# UD3_1_Analog_IO.net
KiCad netlist of a schematic drawn in Altium Designer
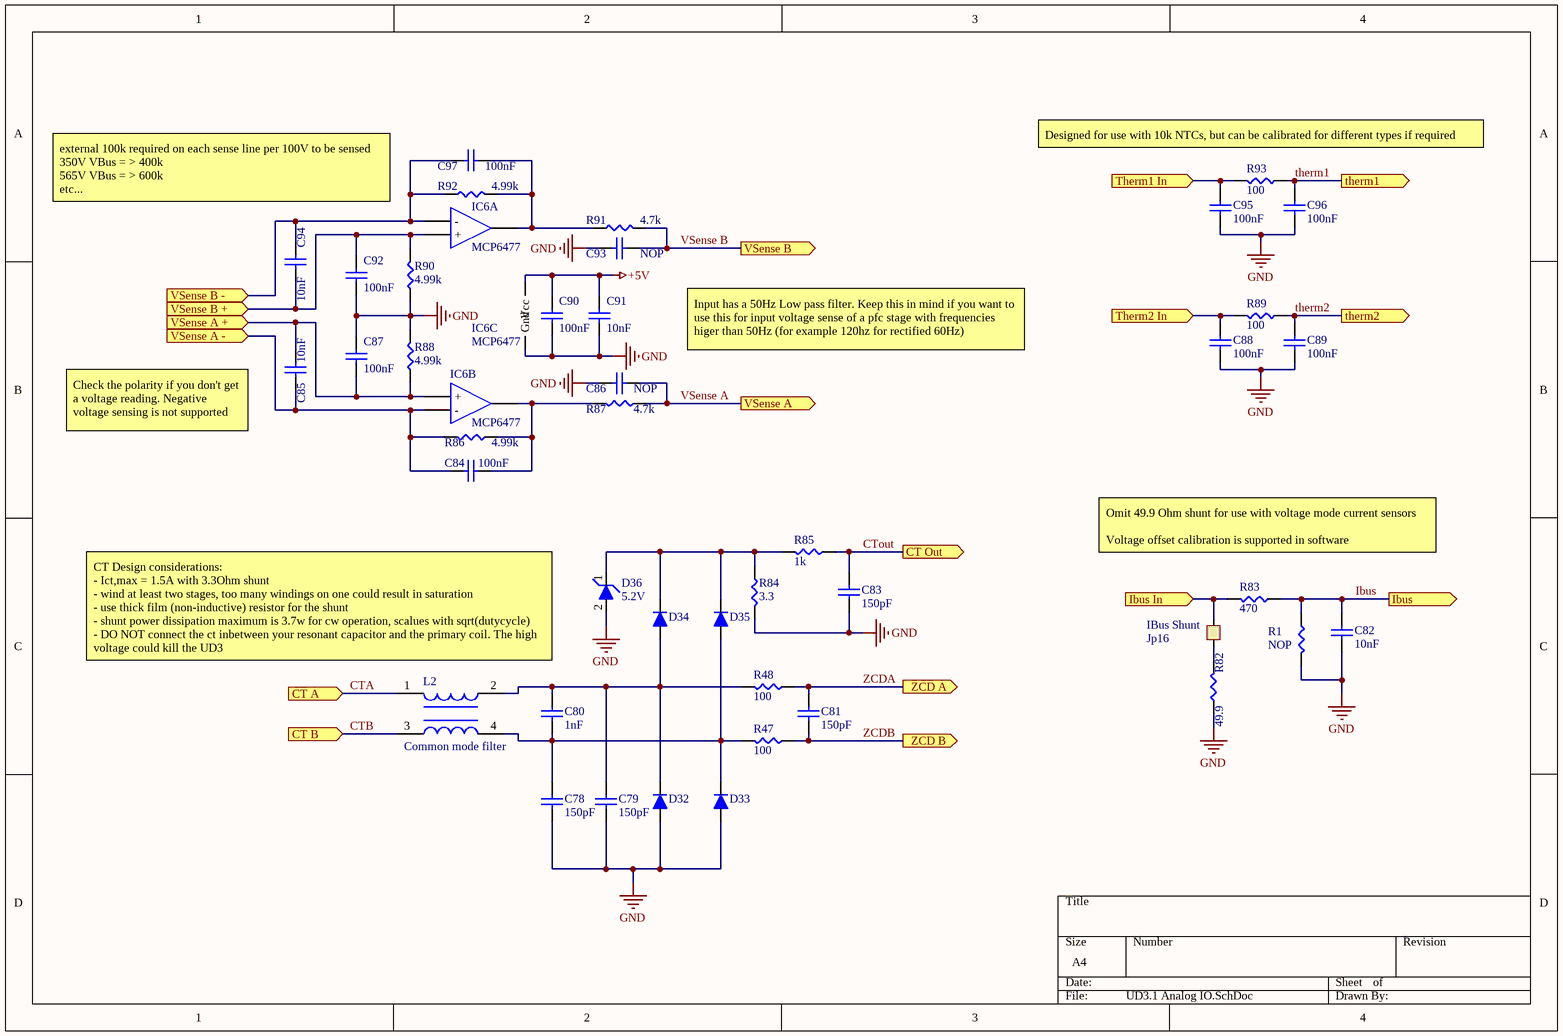
[diagram p0: UD3.1 Analog IO.SchDoc]

(export (version "E")
  (design (tool "Eeschema 10.0.6"))
  (components
    (comp (ref "C78") (value "150pF") (footprint "0603") (libsource (lib "stdLib") (part "Cap")))
    (comp (ref "C79") (value "150pF") (footprint "0603") (libsource (lib "stdLib") (part "Cap")))
    (comp (ref "C80") (value "1nF") (footprint "0603") (libsource (lib "stdLib") (part "Cap")))
    (comp (ref "C81") (value "150pF") (footprint "0603") (libsource (lib "stdLib") (part "Cap")))
    (comp (ref "C82") (value "10nF") (footprint "0603") (libsource (lib "stdLib") (part "Cap")))
    (comp (ref "C83") (value "150pF") (footprint "0603") (libsource (lib "stdLib") (part "Cap")))
    (comp (ref "C84") (value "100nF") (footprint "0603") (libsource (lib "stdLib") (part "Cap")))
    (comp (ref "C85") (value "10nF") (footprint "0603") (libsource (lib "stdLib") (part "Cap")))
    (comp (ref "C86") (value "NOP") (footprint "0603") (libsource (lib "stdLib") (part "Cap")))
    (comp (ref "C87") (value "100nF") (footprint "0603") (libsource (lib "stdLib") (part "Cap")))
    (comp (ref "C88") (value "100nF") (footprint "0603") (libsource (lib "stdLib") (part "Cap")))
    (comp (ref "C89") (value "100nF") (footprint "0603") (libsource (lib "stdLib") (part "Cap")))
    (comp (ref "C90") (value "100nF") (footprint "0603") (libsource (lib "stdLib") (part "Cap")))
    (comp (ref "C91") (value "10nF") (footprint "0603") (libsource (lib "stdLib") (part "Cap")))
    (comp (ref "C92") (value "100nF") (footprint "0603") (libsource (lib "stdLib") (part "Cap")))
    (comp (ref "C93") (value "NOP") (footprint "0603") (libsource (lib "stdLib") (part "Cap")))
    (comp (ref "C94") (value "10nF") (footprint "0603") (libsource (lib "stdLib") (part "Cap")))
    (comp (ref "C95") (value "100nF") (footprint "0603") (libsource (lib "stdLib") (part "Cap")))
    (comp (ref "C96") (value "100nF") (footprint "0603") (libsource (lib "stdLib") (part "Cap")))
    (comp (ref "C97") (value "100nF") (footprint "0603") (libsource (lib "stdLib") (part "Cap")))
    (comp (ref "D32")
      (value "Schottky 30V 1A")
      (footprint "DO-214")
      (description "Cmon its a diode what more do I need to say?")
      (libsource (lib "stdLib") (part "Diode"))
    )
    (comp (ref "D33")
      (value "Schottky 30V 1A")
      (footprint "DO-214")
      (description "Cmon its a diode what more do I need to say?")
      (libsource (lib "stdLib") (part "Diode"))
    )
    (comp (ref "D34")
      (value "Schottky 30V 1A")
      (footprint "DO-214")
      (description "Cmon its a diode what more do I need to say?")
      (libsource (lib "stdLib") (part "Diode"))
    )
    (comp (ref "D35")
      (value "Schottky 30V 1A")
      (footprint "DO-214")
      (description "Cmon its a diode what more do I need to say?")
      (libsource (lib "stdLib") (part "Diode"))
    )
    (comp (ref "D36") (value "5.2V") (footprint "DO-214") (libsource (lib "stdLib") (part "TVS Diode")))
    (comp (ref "IC6") (value "MCP6477") (footprint "soic8") (libsource (lib "stdLib") (part "OpAmp dual")))
    (comp (ref "Jp16")
      (value "IBus Shunt")
      (footprint "PCB Jumper NO")
      (libsource (lib "stdLib") (part "Jumper"))
    )
    (comp (ref "L2")
      (value "Common mode filter")
      (footprint "SON127P600 4 POS (8.50mm x 5.60mm)")
      (libsource (lib "stdLib") (part "Common mode filter"))
    )
    (comp (ref "R1") (value "NOP") (footprint "0603") (libsource (lib "stdLib") (part "Resistor")))
    (comp (ref "R47") (value "100") (footprint "0603") (libsource (lib "stdLib") (part "Resistor")))
    (comp (ref "R48") (value "100") (footprint "0603") (libsource (lib "stdLib") (part "Resistor")))
    (comp (ref "R82") (value "49.9") (footprint "1210") (libsource (lib "stdLib") (part "Resistor")))
    (comp (ref "R83") (value "470") (footprint "0603") (libsource (lib "stdLib") (part "Resistor")))
    (comp (ref "R84") (value "3.3") (footprint "0411 THT 2W") (libsource (lib "stdLib") (part "Resistor")))
    (comp (ref "R85") (value "1k") (footprint "0603") (libsource (lib "stdLib") (part "Resistor")))
    (comp (ref "R86") (value "4.99k") (footprint "0603") (libsource (lib "stdLib") (part "Resistor")))
    (comp (ref "R87") (value "4.7k") (footprint "0603") (libsource (lib "stdLib") (part "Resistor")))
    (comp (ref "R88") (value "4.99k") (footprint "0603") (libsource (lib "stdLib") (part "Resistor")))
    (comp (ref "R89") (value "100") (footprint "0603") (libsource (lib "stdLib") (part "Resistor")))
    (comp (ref "R90") (value "4.99k") (footprint "0603") (libsource (lib "stdLib") (part "Resistor")))
    (comp (ref "R91") (value "4.7k") (footprint "0603") (libsource (lib "stdLib") (part "Resistor")))
    (comp (ref "R92") (value "4.99k") (footprint "0603") (libsource (lib "stdLib") (part "Resistor")))
    (comp (ref "R93") (value "100") (footprint "0603") (libsource (lib "stdLib") (part "Resistor")))
  )
  (nets
    (net (code "1") (name "+5V") (class "Default")
      (node (ref "C90") (pin "2") (pinfunction "2_2") (pintype "passive"))
      (node (ref "C91") (pin "2") (pinfunction "2_2") (pintype "passive"))
      (node (ref "IC6") (pin "8") (pinfunction "Vcc_8") (pintype "passive"))
    )
    (net (code "2") (name "/CTA") (class "Default")
      (node (ref "L2") (pin "1") (pinfunction "1_1") (pintype "passive"))
    )
    (net (code "3") (name "/CTB") (class "Default")
      (node (ref "L2") (pin "3") (pinfunction "1_3") (pintype "passive"))
    )
    (net (code "4") (name "/CTout") (class "Default")
      (node (ref "C83") (pin "1") (pinfunction "1_1") (pintype "passive"))
      (node (ref "R85") (pin "1") (pinfunction "1_1") (pintype "passive"))
    )
    (net (code "5") (name "/Ibus") (class "Default")
      (node (ref "C82") (pin "2") (pinfunction "2_2") (pintype "passive"))
      (node (ref "R1") (pin "1") (pinfunction "1_1") (pintype "passive"))
      (node (ref "R83") (pin "1") (pinfunction "1_1") (pintype "passive"))
    )
    (net (code "6") (name "/Ibus In") (class "Default")
      (node (ref "Jp16") (pin "2") (pinfunction "2_2") (pintype "passive"))
      (node (ref "R83") (pin "2") (pinfunction "2_2") (pintype "passive"))
    )
    (net (code "7") (name "/Therm1 In") (class "Default")
      (node (ref "C95") (pin "2") (pinfunction "2_2") (pintype "passive"))
      (node (ref "R93") (pin "2") (pinfunction "2_2") (pintype "passive"))
    )
    (net (code "8") (name "/Therm2 In") (class "Default")
      (node (ref "C88") (pin "2") (pinfunction "2_2") (pintype "passive"))
      (node (ref "R89") (pin "2") (pinfunction "2_2") (pintype "passive"))
    )
    (net (code "9") (name "/VSense A") (class "Default")
      (node (ref "C86") (pin "2") (pinfunction "2_2") (pintype "passive"))
      (node (ref "R87") (pin "2") (pinfunction "2_2") (pintype "passive"))
    )
    (net (code "10") (name "/VSense A +") (class "Default")
      (node (ref "C85") (pin "2") (pinfunction "2_2") (pintype "passive"))
      (node (ref "C87") (pin "1") (pinfunction "1_1") (pintype "passive"))
      (node (ref "IC6") (pin "5") (pinfunction "+_5") (pintype "passive"))
      (node (ref "R88") (pin "1") (pinfunction "1_1") (pintype "passive"))
    )
    (net (code "11") (name "/VSense A -") (class "Default")
      (node (ref "C84") (pin "1") (pinfunction "1_1") (pintype "passive"))
      (node (ref "C85") (pin "1") (pinfunction "1_1") (pintype "passive"))
      (node (ref "IC6") (pin "6") (pinfunction "-_6") (pintype "passive"))
      (node (ref "R86") (pin "1") (pinfunction "1_1") (pintype "passive"))
    )
    (net (code "12") (name "/VSense B") (class "Default")
      (node (ref "C93") (pin "2") (pinfunction "2_2") (pintype "passive"))
      (node (ref "R91") (pin "2") (pinfunction "2_2") (pintype "passive"))
    )
    (net (code "13") (name "/VSense B +") (class "Default")
      (node (ref "C92") (pin "2") (pinfunction "2_2") (pintype "passive"))
      (node (ref "C94") (pin "1") (pinfunction "1_1") (pintype "passive"))
      (node (ref "IC6") (pin "3") (pinfunction "+_3") (pintype "passive"))
      (node (ref "R90") (pin "2") (pinfunction "2_2") (pintype "passive"))
    )
    (net (code "14") (name "/VSense B -") (class "Default")
      (node (ref "C94") (pin "2") (pinfunction "2_2") (pintype "passive"))
      (node (ref "C97") (pin "1") (pinfunction "1_1") (pintype "passive"))
      (node (ref "IC6") (pin "2") (pinfunction "-_2") (pintype "passive"))
      (node (ref "R92") (pin "1") (pinfunction "1_1") (pintype "passive"))
    )
    (net (code "15") (name "/ZCDA") (class "Default")
      (node (ref "C81") (pin "1") (pinfunction "1_1") (pintype "passive"))
      (node (ref "R48") (pin "1") (pinfunction "1_1") (pintype "passive"))
    )
    (net (code "16") (name "/ZCDB") (class "Default")
      (node (ref "C81") (pin "2") (pinfunction "2_2") (pintype "passive"))
      (node (ref "R47") (pin "1") (pinfunction "1_1") (pintype "passive"))
    )
    (net (code "17") (name "/therm1") (class "Default")
      (node (ref "C96") (pin "2") (pinfunction "2_2") (pintype "passive"))
      (node (ref "R93") (pin "1") (pinfunction "1_1") (pintype "passive"))
    )
    (net (code "18") (name "/therm2") (class "Default")
      (node (ref "C89") (pin "2") (pinfunction "2_2") (pintype "passive"))
      (node (ref "R89") (pin "1") (pinfunction "1_1") (pintype "passive"))
    )
    (net (code "19") (name "GND") (class "Default")
      (node (ref "C78") (pin "2") (pinfunction "2_2") (pintype "passive"))
      (node (ref "C79") (pin "2") (pinfunction "2_2") (pintype "passive"))
      (node (ref "C82") (pin "1") (pinfunction "1_1") (pintype "passive"))
      (node (ref "C83") (pin "2") (pinfunction "2_2") (pintype "passive"))
      (node (ref "C86") (pin "1") (pinfunction "1_1") (pintype "passive"))
      (node (ref "C87") (pin "2") (pinfunction "2_2") (pintype "passive"))
      (node (ref "C88") (pin "1") (pinfunction "1_1") (pintype "passive"))
      (node (ref "C89") (pin "1") (pinfunction "1_1") (pintype "passive"))
      (node (ref "C90") (pin "1") (pinfunction "1_1") (pintype "passive"))
      (node (ref "C91") (pin "1") (pinfunction "1_1") (pintype "passive"))
      (node (ref "C92") (pin "1") (pinfunction "1_1") (pintype "passive"))
      (node (ref "C93") (pin "1") (pinfunction "1_1") (pintype "passive"))
      (node (ref "C95") (pin "1") (pinfunction "1_1") (pintype "passive"))
      (node (ref "C96") (pin "1") (pinfunction "1_1") (pintype "passive"))
      (node (ref "D32") (pin "1") (pintype "passive"))
      (node (ref "D33") (pin "1") (pintype "passive"))
      (node (ref "D36") (pin "2") (pintype "passive"))
      (node (ref "IC6") (pin "4") (pinfunction "Gnd_4") (pintype "passive"))
      (node (ref "R1") (pin "2") (pinfunction "2_2") (pintype "passive"))
      (node (ref "R82") (pin "1") (pinfunction "1_1") (pintype "passive"))
      (node (ref "R84") (pin "2") (pinfunction "2_2") (pintype "passive"))
      (node (ref "R88") (pin "2") (pinfunction "2_2") (pintype "passive"))
      (node (ref "R90") (pin "1") (pinfunction "1_1") (pintype "passive"))
    )
    (net (code "20") (name "Net-(C78-Pad1)") (class "Default")
      (node (ref "C78") (pin "1") (pinfunction "1_1") (pintype "passive"))
      (node (ref "C80") (pin "2") (pinfunction "2_2") (pintype "passive"))
      (node (ref "D33") (pin "2") (pintype "passive"))
      (node (ref "D35") (pin "1") (pintype "passive"))
      (node (ref "L2") (pin "4") (pinfunction "2_4") (pintype "passive"))
      (node (ref "R47") (pin "2") (pinfunction "2_2") (pintype "passive"))
    )
    (net (code "21") (name "Net-(C79-Pad1)") (class "Default")
      (node (ref "C79") (pin "1") (pinfunction "1_1") (pintype "passive"))
      (node (ref "C80") (pin "1") (pinfunction "1_1") (pintype "passive"))
      (node (ref "D32") (pin "2") (pintype "passive"))
      (node (ref "D34") (pin "1") (pintype "passive"))
      (node (ref "L2") (pin "2") (pinfunction "2_2") (pintype "passive"))
      (node (ref "R48") (pin "2") (pinfunction "2_2") (pintype "passive"))
    )
    (net (code "22") (name "Net-(D34-Pad2)") (class "Default")
      (node (ref "D34") (pin "2") (pintype "passive"))
      (node (ref "D35") (pin "2") (pintype "passive"))
      (node (ref "D36") (pin "1") (pintype "passive"))
      (node (ref "R84") (pin "1") (pinfunction "1_1") (pintype "passive"))
      (node (ref "R85") (pin "2") (pinfunction "2_2") (pintype "passive"))
    )
    (net (code "23") (name "Net-(IC6A-Q)") (class "Default")
      (node (ref "C97") (pin "2") (pinfunction "2_2") (pintype "passive"))
      (node (ref "IC6") (pin "1") (pinfunction "Q_1") (pintype "passive"))
      (node (ref "R91") (pin "1") (pinfunction "1_1") (pintype "passive"))
      (node (ref "R92") (pin "2") (pinfunction "2_2") (pintype "passive"))
    )
    (net (code "24") (name "Net-(IC6B-Q)") (class "Default")
      (node (ref "C84") (pin "2") (pinfunction "2_2") (pintype "passive"))
      (node (ref "IC6") (pin "7") (pinfunction "Q_7") (pintype "passive"))
      (node (ref "R86") (pin "2") (pinfunction "2_2") (pintype "passive"))
      (node (ref "R87") (pin "1") (pinfunction "1_1") (pintype "passive"))
    )
    (net (code "25") (name "Net-(Jp16-Pad1)") (class "Default")
      (node (ref "Jp16") (pin "1") (pinfunction "1_1") (pintype "passive"))
      (node (ref "R82") (pin "2") (pinfunction "2_2") (pintype "passive"))
    )
  )
)
